# ETHERNET.net
KiCad netlist of a schematic drawn in Altium Designer
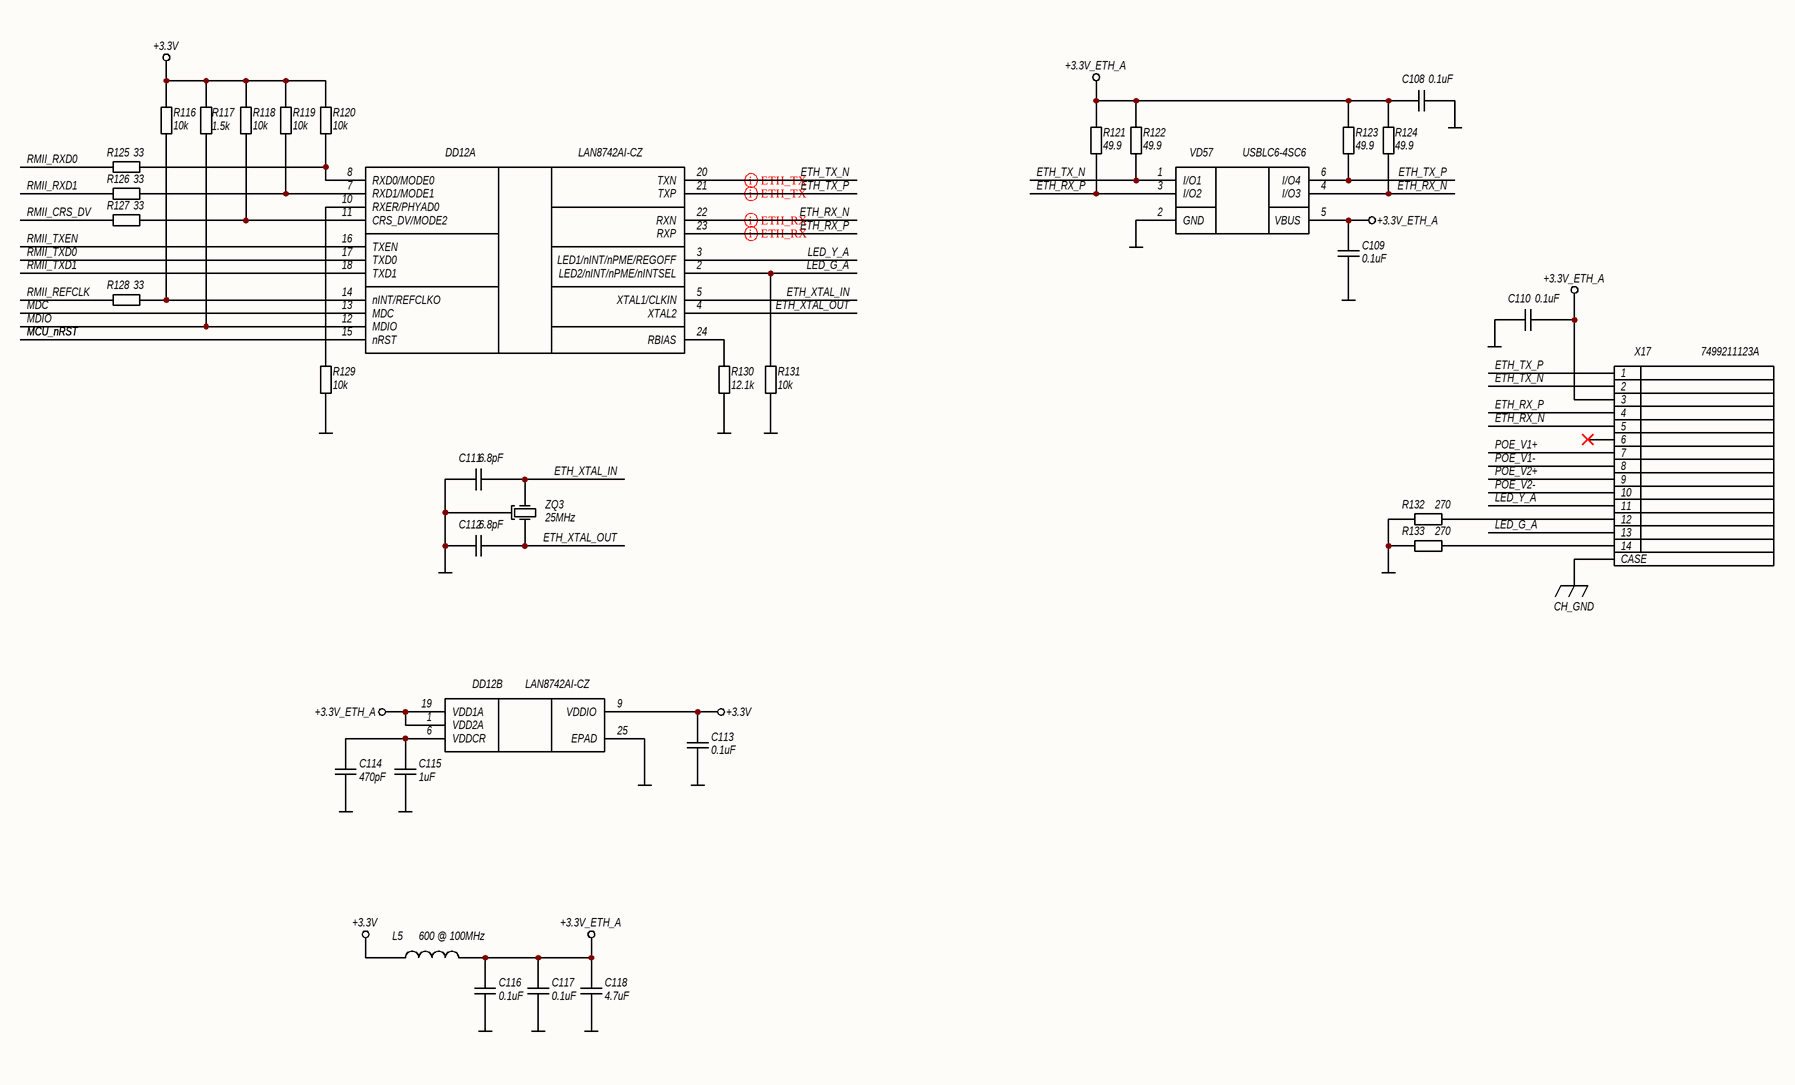
[diagram p0: ETHERNET.SchDoc]

(export (version "E")
  (design (tool "Eeschema 10.0.6"))
  (components
    (comp (ref "C108")
      (value "0.1uF")
      (footprint "C0603N")
      (description "Конденсатор")
      (libsource (lib "Components Library") (part "CAP_FIXED"))
    )
    (comp (ref "C109")
      (value "0.1uF")
      (footprint "C0603N")
      (description "Конденсатор")
      (libsource (lib "Components Library") (part "CAP_FIXED"))
    )
    (comp (ref "C110")
      (value "0.1uF")
      (footprint "C0603N")
      (description "Конденсатор")
      (libsource (lib "Components Library") (part "CAP_FIXED"))
    )
    (comp (ref "C111")
      (value "6.8pF")
      (footprint "C0603N")
      (description "Конденсатор")
      (libsource (lib "Components Library") (part "CAP_FIXED"))
    )
    (comp (ref "C112")
      (value "6.8pF")
      (footprint "C0603N")
      (description "Конденсатор")
      (libsource (lib "Components Library") (part "CAP_FIXED"))
    )
    (comp (ref "C113")
      (value "0.1uF")
      (footprint "C0603N")
      (description "Конденсатор")
      (libsource (lib "Components Library") (part "CAP_FIXED"))
    )
    (comp (ref "C114")
      (value "470pF")
      (footprint "C0603N")
      (description "Конденсатор")
      (libsource (lib "Components Library") (part "CAP_FIXED"))
    )
    (comp (ref "C115")
      (value "1uF")
      (footprint "C0603N")
      (description "Конденсатор")
      (libsource (lib "Components Library") (part "CAP_FIXED"))
    )
    (comp (ref "C116")
      (value "0.1uF")
      (footprint "C0603N")
      (description "Конденсатор")
      (libsource (lib "Components Library") (part "CAP_FIXED"))
    )
    (comp (ref "C117")
      (value "0.1uF")
      (footprint "C0603N")
      (description "Конденсатор")
      (libsource (lib "Components Library") (part "CAP_FIXED"))
    )
    (comp (ref "C118")
      (value "4.7uF")
      (footprint "C0603N")
      (description "Конденсатор")
      (libsource (lib "Components Library") (part "CAP_FIXED"))
    )
    (comp (ref "DD12")
      (value "LAN8742AI-CZ")
      (footprint "S4QFN-24")
      (description "Микросхема физического уровня Ethernet 10/100, RMII")
      (libsource (lib "Components Library") (part "LAN8742Ax"))
    )
    (comp (ref "L5")
      (value "600 @ 100MHz")
      (footprint "FB0603N")
      (description "Фильтр ЭМП индуктивный")
      (libsource (lib "Components Library") (part "IND_FILTER"))
    )
    (comp (ref "R116")
      (value "10k")
      (footprint "R0603N")
      (description "Резистор")
      (libsource (lib "Components Library") (part "RES_FIXED"))
    )
    (comp (ref "R117")
      (value "1.5k")
      (footprint "R0603N")
      (description "Резистор")
      (libsource (lib "Components Library") (part "RES_FIXED"))
    )
    (comp (ref "R118")
      (value "10k")
      (footprint "R0603N")
      (description "Резистор")
      (libsource (lib "Components Library") (part "RES_FIXED"))
    )
    (comp (ref "R119")
      (value "10k")
      (footprint "R0603N")
      (description "Резистор")
      (libsource (lib "Components Library") (part "RES_FIXED"))
    )
    (comp (ref "R120")
      (value "10k")
      (footprint "R0603N")
      (description "Резистор")
      (libsource (lib "Components Library") (part "RES_FIXED"))
    )
    (comp (ref "R121")
      (value "49.9")
      (footprint "R0603N")
      (description "Резистор")
      (libsource (lib "") (part "RES_FIXED_3"))
    )
    (comp (ref "R122")
      (value "49.9")
      (footprint "R0603N")
      (description "Резистор")
      (libsource (lib "") (part "RES_FIXED_3"))
    )
    (comp (ref "R123")
      (value "49.9")
      (footprint "R0603N")
      (description "Резистор")
      (libsource (lib "") (part "RES_FIXED_3"))
    )
    (comp (ref "R124")
      (value "49.9")
      (footprint "R0603N")
      (description "Резистор")
      (libsource (lib "") (part "RES_FIXED_3"))
    )
    (comp (ref "R125")
      (value "33")
      (footprint "R0603N")
      (description "Резистор")
      (libsource (lib "") (part "RES_FIXED_1"))
    )
    (comp (ref "R126")
      (value "33")
      (footprint "R0603N")
      (description "Резистор")
      (libsource (lib "") (part "RES_FIXED_1"))
    )
    (comp (ref "R127")
      (value "33")
      (footprint "R0603N")
      (description "Резистор")
      (libsource (lib "") (part "RES_FIXED_1"))
    )
    (comp (ref "R128")
      (value "33")
      (footprint "R0603N")
      (description "Резистор")
      (libsource (lib "") (part "RES_FIXED_1"))
    )
    (comp (ref "R129")
      (value "10k")
      (footprint "R0603N")
      (description "Резистор")
      (libsource (lib "") (part "RES_FIXED_3"))
    )
    (comp (ref "R130")
      (value "12.1k")
      (footprint "R0603N")
      (description "Резистор")
      (libsource (lib "") (part "RES_FIXED_3"))
    )
    (comp (ref "R131")
      (value "10k")
      (footprint "R0603N")
      (description "Резистор")
      (libsource (lib "") (part "RES_FIXED_3"))
    )
    (comp (ref "R132")
      (value "270")
      (footprint "R0603N")
      (description "Резистор")
      (libsource (lib "") (part "RES_FIXED_2"))
    )
    (comp (ref "R133")
      (value "270")
      (footprint "R0603N")
      (description "Резистор")
      (libsource (lib "") (part "RES_FIXED_2"))
    )
    (comp (ref "VD57")
      (value "USBLC6-4SC6")
      (footprint "SOT23-6")
      (description "Сборка TVS диодов, 4-канальная")
      (libsource (lib "Components Library") (part "USBLC6-4"))
    )
    (comp (ref "X17")
      (value "7499211123A")
      (footprint "7499211123A")
      (description "Разъем, 14 контактов+корпус")
      (libsource (lib "Components Library") (part "Connector 14+C"))
    )
    (comp (ref "ZQ3")
      (value "25MHz")
      (footprint "NX3225GA")
      (description "Кварцевый резонатор, экранированный")
      (libsource (lib "Components Library") (part "RESONATOR_3PIN"))
    )
  )
  (nets
    (net (code "1") (name "+3.3V") (class "Default")
      (node (ref "C113") (pin "2") (pinfunction "2_2") (pintype "passive"))
      (node (ref "DD12") (pin "9") (pinfunction "VDDIO_9") (pintype "power_in"))
      (node (ref "L5") (pin "1") (pinfunction "1_1") (pintype "passive"))
      (node (ref "R116") (pin "1") (pinfunction "1_1") (pintype "passive"))
      (node (ref "R117") (pin "1") (pinfunction "1_1") (pintype "passive"))
      (node (ref "R118") (pin "1") (pinfunction "1_1") (pintype "passive"))
      (node (ref "R119") (pin "1") (pinfunction "1_1") (pintype "passive"))
      (node (ref "R120") (pin "1") (pinfunction "1_1") (pintype "passive"))
    )
    (net (code "2") (name "+3.3V_ETH_A") (class "Default")
      (node (ref "C108") (pin "2") (pinfunction "2_2") (pintype "passive"))
      (node (ref "C109") (pin "2") (pinfunction "2_2") (pintype "passive"))
      (node (ref "C110") (pin "1") (pinfunction "1_1") (pintype "passive"))
      (node (ref "C116") (pin "2") (pinfunction "2_2") (pintype "passive"))
      (node (ref "C117") (pin "2") (pinfunction "2_2") (pintype "passive"))
      (node (ref "C118") (pin "2") (pinfunction "2_2") (pintype "passive"))
      (node (ref "DD12") (pin "1") (pinfunction "VDD2A_1") (pintype "passive"))
      (node (ref "DD12") (pin "19") (pinfunction "VDD1A_19") (pintype "power_in"))
      (node (ref "L5") (pin "2") (pinfunction "2_2") (pintype "passive"))
      (node (ref "R121") (pin "2") (pinfunction "2_2") (pintype "passive"))
      (node (ref "R122") (pin "2") (pinfunction "2_2") (pintype "passive"))
      (node (ref "R123") (pin "2") (pinfunction "2_2") (pintype "passive"))
      (node (ref "R124") (pin "2") (pinfunction "2_2") (pintype "passive"))
      (node (ref "VD57") (pin "5") (pinfunction "VBUS_5") (pintype "power_in"))
      (node (ref "X17") (pin "3") (pinfunction "3_3") (pintype "power_in"))
    )
    (net (code "3") (name "/ETH_RX_N") (class "Default")
      (node (ref "DD12") (pin "22") (pinfunction "RXN_22") (pintype "power_in"))
      (node (ref "R124") (pin "1") (pinfunction "1_1") (pintype "passive"))
      (node (ref "VD57") (pin "4") (pinfunction "I/O3_4") (pintype "power_in"))
      (node (ref "X17") (pin "5") (pinfunction "5_5") (pintype "power_in"))
    )
    (net (code "4") (name "/ETH_RX_P") (class "Default")
      (node (ref "DD12") (pin "23") (pinfunction "RXP_23") (pintype "power_in"))
      (node (ref "R121") (pin "1") (pinfunction "1_1") (pintype "passive"))
      (node (ref "VD57") (pin "3") (pinfunction "I/O2_3") (pintype "power_in"))
      (node (ref "X17") (pin "4") (pinfunction "4_4") (pintype "power_in"))
    )
    (net (code "5") (name "/ETH_TX_N") (class "Default")
      (node (ref "DD12") (pin "20") (pinfunction "TXN_20") (pintype "power_in"))
      (node (ref "R122") (pin "1") (pinfunction "1_1") (pintype "passive"))
      (node (ref "VD57") (pin "1") (pinfunction "I/O1_1") (pintype "power_in"))
      (node (ref "X17") (pin "2") (pinfunction "2_2") (pintype "power_in"))
    )
    (net (code "6") (name "/ETH_TX_P") (class "Default")
      (node (ref "DD12") (pin "21") (pinfunction "TXP_21") (pintype "power_in"))
      (node (ref "R123") (pin "1") (pinfunction "1_1") (pintype "passive"))
      (node (ref "VD57") (pin "6") (pinfunction "I/O4_6") (pintype "power_in"))
      (node (ref "X17") (pin "1") (pinfunction "1_1") (pintype "power_in"))
    )
    (net (code "7") (name "/ETH_XTAL_IN") (class "Default")
      (node (ref "C111") (pin "1") (pinfunction "1_1") (pintype "passive"))
      (node (ref "DD12") (pin "5") (pinfunction "XTAL1/CLKIN_5") (pintype "passive"))
      (node (ref "ZQ3") (pin "1") (pinfunction "1_1") (pintype "passive"))
    )
    (net (code "8") (name "/ETH_XTAL_OUT") (class "Default")
      (node (ref "C112") (pin "1") (pinfunction "1_1") (pintype "passive"))
      (node (ref "DD12") (pin "4") (pinfunction "XTAL2_4") (pintype "passive"))
      (node (ref "ZQ3") (pin "3") (pinfunction "3_3") (pintype "passive"))
    )
    (net (code "9") (name "/LED_G_A") (class "Default")
      (node (ref "DD12") (pin "2") (pinfunction "LED2/nINT/nPME/nINTSEL_2") (pintype "passive"))
      (node (ref "R131") (pin "2") (pinfunction "2_2") (pintype "passive"))
      (node (ref "X17") (pin "13") (pinfunction "13_13") (pintype "power_in"))
    )
    (net (code "10") (name "/LED_Y_A") (class "Default")
      (node (ref "DD12") (pin "3") (pinfunction "LED1/nINT/nPME/REGOFF_3") (pintype "passive"))
      (node (ref "X17") (pin "11") (pinfunction "11_11") (pintype "power_in"))
    )
    (net (code "11") (name "/MCU_nRST") (class "Default")
      (node (ref "DD12") (pin "15") (pinfunction "nRST_15") (pintype "power_in"))
    )
    (net (code "12") (name "/MDC") (class "Default")
      (node (ref "DD12") (pin "13") (pinfunction "MDC_13") (pintype "power_in"))
    )
    (net (code "13") (name "/MDIO") (class "Default")
      (node (ref "DD12") (pin "12") (pinfunction "MDIO_12") (pintype "power_in"))
      (node (ref "R117") (pin "2") (pinfunction "2_2") (pintype "passive"))
    )
    (net (code "14") (name "/POE_V1+") (class "Default")
      (node (ref "X17") (pin "7") (pinfunction "7_7") (pintype "power_in"))
    )
    (net (code "15") (name "/POE_V1-") (class "Default")
      (node (ref "X17") (pin "8") (pinfunction "8_8") (pintype "power_in"))
    )
    (net (code "16") (name "/POE_V2+") (class "Default")
      (node (ref "X17") (pin "9") (pinfunction "9_9") (pintype "power_in"))
    )
    (net (code "17") (name "/POE_V2-") (class "Default")
      (node (ref "X17") (pin "10") (pinfunction "10_10") (pintype "power_in"))
    )
    (net (code "18") (name "/RMII_CRS_DV") (class "Default")
      (node (ref "R127") (pin "2") (pinfunction "2_2") (pintype "passive"))
    )
    (net (code "19") (name "/RMII_REFCLK") (class "Default")
      (node (ref "R128") (pin "2") (pinfunction "2_2") (pintype "passive"))
    )
    (net (code "20") (name "/RMII_RXD0") (class "Default")
      (node (ref "R125") (pin "2") (pinfunction "2_2") (pintype "passive"))
    )
    (net (code "21") (name "/RMII_RXD1") (class "Default")
      (node (ref "R126") (pin "2") (pinfunction "2_2") (pintype "passive"))
    )
    (net (code "22") (name "/RMII_TXD0") (class "Default")
      (node (ref "DD12") (pin "17") (pinfunction "TXD0_17") (pintype "power_in"))
    )
    (net (code "23") (name "/RMII_TXD1") (class "Default")
      (node (ref "DD12") (pin "18") (pinfunction "TXD1_18") (pintype "power_in"))
    )
    (net (code "24") (name "/RMII_TXEN") (class "Default")
      (node (ref "DD12") (pin "16") (pinfunction "TXEN_16") (pintype "power_in"))
    )
    (net (code "25") (name "CH_GND") (class "Default")
      (node (ref "X17") (pin "15") (pinfunction "CASE_15") (pintype "power_in"))
    )
    (net (code "26") (name "GND") (class "Default")
      (node (ref "C108") (pin "1") (pinfunction "1_1") (pintype "passive"))
      (node (ref "C109") (pin "1") (pinfunction "1_1") (pintype "passive"))
      (node (ref "C110") (pin "2") (pinfunction "2_2") (pintype "passive"))
      (node (ref "C111") (pin "2") (pinfunction "2_2") (pintype "passive"))
      (node (ref "C112") (pin "2") (pinfunction "2_2") (pintype "passive"))
      (node (ref "C113") (pin "1") (pinfunction "1_1") (pintype "passive"))
      (node (ref "C114") (pin "1") (pinfunction "1_1") (pintype "passive"))
      (node (ref "C115") (pin "1") (pinfunction "1_1") (pintype "passive"))
      (node (ref "C116") (pin "1") (pinfunction "1_1") (pintype "passive"))
      (node (ref "C117") (pin "1") (pinfunction "1_1") (pintype "passive"))
      (node (ref "C118") (pin "1") (pinfunction "1_1") (pintype "passive"))
      (node (ref "DD12") (pin "25") (pinfunction "EPAD_25") (pintype "power_in"))
      (node (ref "R129") (pin "1") (pinfunction "1_1") (pintype "passive"))
      (node (ref "R130") (pin "1") (pinfunction "1_1") (pintype "passive"))
      (node (ref "R131") (pin "1") (pinfunction "1_1") (pintype "passive"))
      (node (ref "R132") (pin "1") (pinfunction "1_1") (pintype "passive"))
      (node (ref "R133") (pin "1") (pinfunction "1_1") (pintype "passive"))
      (node (ref "VD57") (pin "2") (pinfunction "GND_2") (pintype "power_in"))
      (node (ref "ZQ3") (pin "2") (pinfunction "2_2") (pintype "passive"))
    )
    (net (code "27") (name "Net-(DD12A-CRS_DV{slash}MODE2)") (class "Default")
      (node (ref "DD12") (pin "11") (pinfunction "CRS_DV/MODE2_11") (pintype "power_in"))
      (node (ref "R118") (pin "2") (pinfunction "2_2") (pintype "passive"))
      (node (ref "R127") (pin "1") (pinfunction "1_1") (pintype "passive"))
    )
    (net (code "28") (name "Net-(DD12A-RBIAS)") (class "Default")
      (node (ref "DD12") (pin "24") (pinfunction "RBIAS_24") (pintype "power_in"))
      (node (ref "R130") (pin "2") (pinfunction "2_2") (pintype "passive"))
    )
    (net (code "29") (name "Net-(DD12A-RXD0{slash}MODE0)") (class "Default")
      (node (ref "DD12") (pin "8") (pinfunction "RXD0/MODE0_8") (pintype "power_in"))
      (node (ref "R120") (pin "2") (pinfunction "2_2") (pintype "passive"))
      (node (ref "R125") (pin "1") (pinfunction "1_1") (pintype "passive"))
    )
    (net (code "30") (name "Net-(DD12A-RXD1{slash}MODE1)") (class "Default")
      (node (ref "DD12") (pin "7") (pinfunction "RXD1/MODE1_7") (pintype "power_in"))
      (node (ref "R119") (pin "2") (pinfunction "2_2") (pintype "passive"))
      (node (ref "R126") (pin "1") (pinfunction "1_1") (pintype "passive"))
    )
    (net (code "31") (name "Net-(DD12A-RXER{slash}PHYAD0)") (class "Default")
      (node (ref "DD12") (pin "10") (pinfunction "RXER/PHYAD0_10") (pintype "power_in"))
      (node (ref "R129") (pin "2") (pinfunction "2_2") (pintype "passive"))
    )
    (net (code "32") (name "Net-(DD12A-nINT{slash}REFCLKO)") (class "Default")
      (node (ref "DD12") (pin "14") (pinfunction "nINT/REFCLKO_14") (pintype "power_in"))
      (node (ref "R116") (pin "2") (pinfunction "2_2") (pintype "passive"))
      (node (ref "R128") (pin "1") (pinfunction "1_1") (pintype "passive"))
    )
    (net (code "33") (name "Net-(DD12B-VDDCR)") (class "Default")
      (node (ref "C114") (pin "2") (pinfunction "2_2") (pintype "passive"))
      (node (ref "C115") (pin "2") (pinfunction "2_2") (pintype "passive"))
      (node (ref "DD12") (pin "6") (pinfunction "VDDCR_6") (pintype "passive"))
    )
    (net (code "34") (name "Net-(R132-Pad2)") (class "Default")
      (node (ref "R132") (pin "2") (pinfunction "2_2") (pintype "passive"))
      (node (ref "X17") (pin "12") (pinfunction "12_12") (pintype "power_in"))
    )
    (net (code "35") (name "Net-(R133-Pad2)") (class "Default")
      (node (ref "R133") (pin "2") (pinfunction "2_2") (pintype "passive"))
      (node (ref "X17") (pin "14") (pinfunction "14_14") (pintype "power_in"))
    )
    (net (code "36") (name "unconnected-(X17-Pad6)") (class "Default")
      (node (ref "X17") (pin "6") (pinfunction "6_6") (pintype "power_in+no_connect"))
    )
  )
)
